# 165EVAL_REV_B.net
KiCad netlist of a schematic drawn in EAGLE
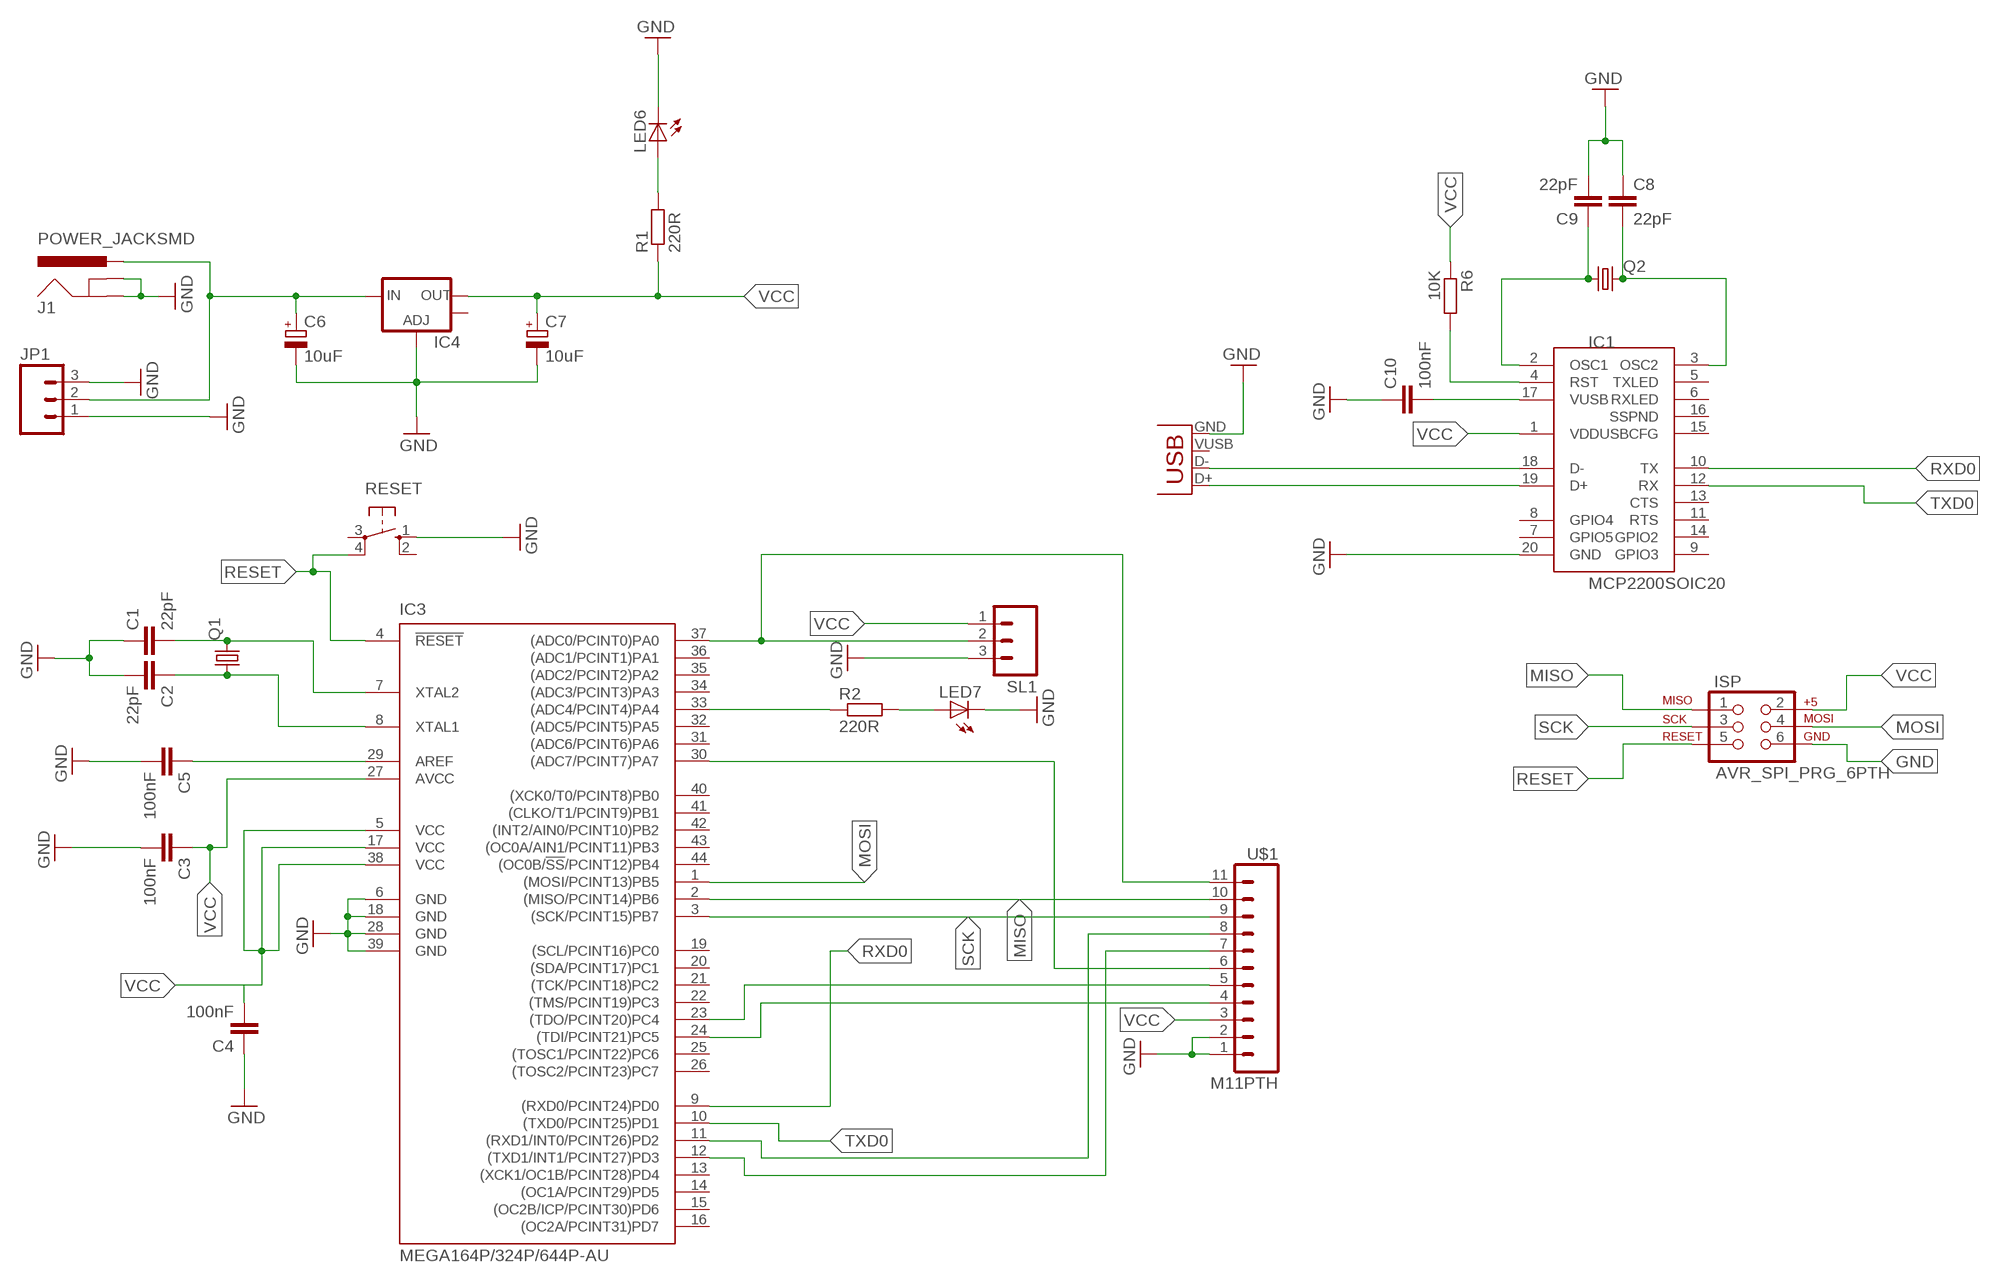
[diagram p0: schematic, sheet 1]

(export (version "E")
  (design (tool "Eeschema 10.0.6"))
  (components
    (comp (ref "C1")
      (value "22pF")
      (footprint "eagle-import:C0805K")
      (libsource (lib "eagle-import") (part "C-EUC0805K"))
    )
    (comp (ref "C2")
      (value "22pF")
      (footprint "eagle-import:C0805K")
      (libsource (lib "eagle-import") (part "C-EUC0805K"))
    )
    (comp (ref "C3")
      (value "100nF")
      (footprint "eagle-import:C0805K")
      (libsource (lib "eagle-import") (part "C-EUC0805K"))
    )
    (comp (ref "C4")
      (value "100nF")
      (footprint "eagle-import:C0805K")
      (libsource (lib "eagle-import") (part "C-EUC0805K"))
    )
    (comp (ref "C5")
      (value "100nF")
      (footprint "eagle-import:C0805K")
      (libsource (lib "eagle-import") (part "C-EUC0805K"))
    )
    (comp (ref "C6")
      (value "10uF")
      (footprint "eagle-import:CT6032")
      (libsource (lib "eagle-import") (part "CPOL-EUCT6032"))
    )
    (comp (ref "C7")
      (value "10uF")
      (footprint "eagle-import:CT6032")
      (libsource (lib "eagle-import") (part "CPOL-EUCT6032"))
    )
    (comp (ref "C8")
      (value "22pF")
      (footprint "eagle-import:C0805K")
      (libsource (lib "eagle-import") (part "C-EUC0805K"))
    )
    (comp (ref "C9")
      (value "22pF")
      (footprint "eagle-import:C0805K")
      (libsource (lib "eagle-import") (part "C-EUC0805K"))
    )
    (comp (ref "C10")
      (value "100nF")
      (footprint "eagle-import:C0805K")
      (libsource (lib "eagle-import") (part "C-EUC0805K"))
    )
    (comp (ref "IC1")
      (value "MCP2200SOIC20")
      (footprint "eagle-import:SOIC20")
      (libsource (lib "eagle-import") (part "MCP2200SOIC20"))
    )
    (comp (ref "IC3")
      (value "MEGA164P/324P/644P-AU")
      (footprint "eagle-import:TQFP44")
      (libsource (lib "eagle-import") (part "MEGA164P/324P/644P-AU"))
    )
    (comp (ref "IC4")
      (value "V_REG_LM1117SOT223")
      (footprint "eagle-import:SOT223")
      (libsource (lib "eagle-import") (part "V_REG_LM1117SOT223"))
    )
    (comp (ref "ISP")
      (value "AVR_SPI_PRG_6PTH")
      (footprint "eagle-import:2X3")
      (libsource (lib "eagle-import") (part "AVR_SPI_PRG_6PTH"))
    )
    (comp (ref "J1")
      (value "POWER_JACKSMD")
      (footprint "eagle-import:POWER_JACK_SMD")
      (libsource (lib "eagle-import") (part "POWER_JACKSMD"))
    )
    (comp (ref "JP1")
      (value "M03PTH")
      (footprint "eagle-import:1X03")
      (libsource (lib "eagle-import") (part "M03PTH"))
    )
    (comp (ref "LED6")
      (value "LEDSMT1206")
      (footprint "eagle-import:1206")
      (libsource (lib "eagle-import") (part "LEDSMT1206"))
    )
    (comp (ref "LED7")
      (value "LEDSMT1206")
      (footprint "eagle-import:1206")
      (libsource (lib "eagle-import") (part "LEDSMT1206"))
    )
    (comp (ref "Q1")
      (value "CRYSTALSM49")
      (footprint "eagle-import:SM49")
      (libsource (lib "eagle-import") (part "CRYSTALSM49"))
    )
    (comp (ref "Q2")
      (value "CRYSTALSM49")
      (footprint "eagle-import:SM49")
      (libsource (lib "eagle-import") (part "CRYSTALSM49"))
    )
    (comp (ref "R1")
      (value "220R")
      (footprint "eagle-import:R1206")
      (libsource (lib "eagle-import") (part "R-EU_R1206"))
    )
    (comp (ref "R2")
      (value "220R")
      (footprint "eagle-import:R1206")
      (libsource (lib "eagle-import") (part "R-EU_R1206"))
    )
    (comp (ref "R6")
      (value "10K")
      (footprint "eagle-import:R1206")
      (libsource (lib "eagle-import") (part "R-EU_R1206"))
    )
    (comp (ref "RESET")
      (value "10-XX")
      (footprint "eagle-import:B3F-10XX")
      (fields (field (name "MPN") "B3F-1000"))
      (libsource (lib "eagle-import") (part "10-XX"))
    )
    (comp (ref "SL1")
      (value "M03")
      (footprint "eagle-import:03P")
      (libsource (lib "eagle-import") (part "M03"))
    )
    (comp (ref "U$1")
      (value "M11PTH")
      (footprint "eagle-import:1X11")
      (libsource (lib "eagle-import") (part "M11PTH"))
    )
    (comp (ref "USB")
      (value "USB-B-S")
      (footprint "eagle-import:USB-B-SMT")
      (libsource (lib "eagle-import") (part "USB-B-S"))
    )
  )
  (nets
    (net (code "1") (name "GND") (class "Default")
      (node (ref "C1") (pin "1") (pinfunction "1_1") (pintype "passive"))
      (node (ref "C10") (pin "1") (pinfunction "1_1") (pintype "passive"))
      (node (ref "C2") (pin "2") (pinfunction "2_2") (pintype "passive"))
      (node (ref "C3") (pin "2") (pinfunction "2_2") (pintype "passive"))
      (node (ref "C4") (pin "1") (pinfunction "1_1") (pintype "passive"))
      (node (ref "C5") (pin "2") (pinfunction "2_2") (pintype "passive"))
      (node (ref "C6") (pin "-") (pinfunction "-_-") (pintype "passive"))
      (node (ref "C7") (pin "-") (pinfunction "-_-") (pintype "passive"))
      (node (ref "C8") (pin "1") (pinfunction "1_1") (pintype "passive"))
      (node (ref "C9") (pin "2") (pinfunction "2_2") (pintype "passive"))
      (node (ref "IC1") (pin "20") (pinfunction "GND_20") (pintype "bidirectional"))
      (node (ref "IC3") (pin "18") (pinfunction "GND_18") (pintype "power_in"))
      (node (ref "IC3") (pin "28") (pinfunction "GND_28") (pintype "power_in"))
      (node (ref "IC3") (pin "39") (pinfunction "GND_39") (pintype "power_in"))
      (node (ref "IC3") (pin "6") (pinfunction "GND_6") (pintype "power_in"))
      (node (ref "IC4") (pin "1") (pinfunction "ADJ_1") (pintype "input"))
      (node (ref "ISP") (pin "6") (pinfunction "6_6") (pintype "passive"))
      (node (ref "J1") (pin "GND") (pinfunction "GNDBREAK_GND") (pintype "bidirectional"))
      (node (ref "J1") (pin "P$4") (pinfunction "GND_P$4") (pintype "bidirectional"))
      (node (ref "JP1") (pin "1") (pinfunction "1_1") (pintype "passive"))
      (node (ref "JP1") (pin "3") (pinfunction "3_3") (pintype "passive"))
      (node (ref "LED6") (pin "C") (pinfunction "C_C") (pintype "passive"))
      (node (ref "LED7") (pin "C") (pinfunction "C_C") (pintype "passive"))
      (node (ref "RESET") (pin "1") (pinfunction "S_1") (pintype "passive"))
      (node (ref "SL1") (pin "3") (pinfunction "3_3") (pintype "passive"))
      (node (ref "U$1") (pin "1") (pinfunction "1_1") (pintype "passive"))
      (node (ref "U$1") (pin "2") (pinfunction "2_2") (pintype "passive"))
      (node (ref "USB") (pin "GND") (pinfunction "GND_GND") (pintype "bidirectional"))
    )
    (net (code "2") (name "MISO") (class "Default")
      (node (ref "IC3") (pin "2") (pinfunction "(MISO/PCINT14)PB6_2") (pintype "bidirectional"))
      (node (ref "ISP") (pin "1") (pinfunction "1_1") (pintype "passive"))
      (node (ref "U$1") (pin "10") (pinfunction "10_10") (pintype "passive"))
    )
    (net (code "3") (name "MOSI") (class "Default")
      (node (ref "IC3") (pin "1") (pinfunction "(MOSI/PCINT13)PB5_1") (pintype "bidirectional"))
      (node (ref "ISP") (pin "4") (pinfunction "4_4") (pintype "passive"))
    )
    (net (code "4") (name "Net-(IC1-D+)") (class "Default")
      (node (ref "IC1") (pin "19") (pinfunction "D+_19") (pintype "bidirectional"))
      (node (ref "USB") (pin "D+") (pinfunction "D+_D+") (pintype "bidirectional"))
    )
    (net (code "5") (name "Net-(IC1-D-)") (class "Default")
      (node (ref "IC1") (pin "18") (pinfunction "D-_18") (pintype "bidirectional"))
      (node (ref "USB") (pin "D-") (pinfunction "D-_D-") (pintype "bidirectional"))
    )
    (net (code "6") (name "Net-(IC1-OSC1)") (class "Default")
      (node (ref "C9") (pin "1") (pinfunction "1_1") (pintype "passive"))
      (node (ref "IC1") (pin "2") (pinfunction "OSC1_2") (pintype "bidirectional"))
      (node (ref "Q2") (pin "1") (pinfunction "1_1") (pintype "passive"))
    )
    (net (code "7") (name "Net-(IC1-OSC2)") (class "Default")
      (node (ref "C8") (pin "2") (pinfunction "2_2") (pintype "passive"))
      (node (ref "IC1") (pin "3") (pinfunction "OSC2_3") (pintype "bidirectional"))
      (node (ref "Q2") (pin "2") (pinfunction "2_2") (pintype "passive"))
    )
    (net (code "8") (name "Net-(IC1-RST)") (class "Default")
      (node (ref "IC1") (pin "4") (pinfunction "RST_4") (pintype "bidirectional"))
      (node (ref "R6") (pin "2") (pinfunction "2_2") (pintype "passive"))
    )
    (net (code "9") (name "Net-(IC1-VUSB)") (class "Default")
      (node (ref "C10") (pin "2") (pinfunction "2_2") (pintype "passive"))
      (node (ref "IC1") (pin "17") (pinfunction "VUSB_17") (pintype "bidirectional"))
    )
    (net (code "10") (name "Net-(IC3-(ADC0{slash}PCINT0)PA0)") (class "Default")
      (node (ref "IC3") (pin "37") (pinfunction "(ADC0/PCINT0)PA0_37") (pintype "bidirectional"))
      (node (ref "SL1") (pin "2") (pinfunction "2_2") (pintype "passive"))
      (node (ref "U$1") (pin "11") (pinfunction "11_11") (pintype "passive"))
    )
    (net (code "11") (name "Net-(IC3-(ADC4{slash}PCINT4)PA4)") (class "Default")
      (node (ref "IC3") (pin "33") (pinfunction "(ADC4/PCINT4)PA4_33") (pintype "bidirectional"))
      (node (ref "R2") (pin "1") (pinfunction "1_1") (pintype "passive"))
    )
    (net (code "12") (name "Net-(IC3-(ADC7{slash}PCINT7)PA7)") (class "Default")
      (node (ref "IC3") (pin "30") (pinfunction "(ADC7/PCINT7)PA7_30") (pintype "bidirectional"))
      (node (ref "U$1") (pin "6") (pinfunction "6_6") (pintype "passive"))
    )
    (net (code "13") (name "Net-(IC3-(RXD1{slash}INT0{slash}PCINT26)PD2)") (class "Default")
      (node (ref "IC3") (pin "11") (pinfunction "(RXD1/INT0/PCINT26)PD2_11") (pintype "bidirectional"))
      (node (ref "U$1") (pin "8") (pinfunction "8_8") (pintype "passive"))
    )
    (net (code "14") (name "Net-(IC3-(TDI{slash}PCINT21)PC5)") (class "Default")
      (node (ref "IC3") (pin "24") (pinfunction "(TDI/PCINT21)PC5_24") (pintype "bidirectional"))
      (node (ref "U$1") (pin "4") (pinfunction "4_4") (pintype "passive"))
    )
    (net (code "15") (name "Net-(IC3-(TDO{slash}PCINT20)PC4)") (class "Default")
      (node (ref "IC3") (pin "23") (pinfunction "(TDO/PCINT20)PC4_23") (pintype "bidirectional"))
      (node (ref "U$1") (pin "5") (pinfunction "5_5") (pintype "passive"))
    )
    (net (code "16") (name "Net-(IC3-(TXD1{slash}INT1{slash}PCINT27)PD3)") (class "Default")
      (node (ref "IC3") (pin "12") (pinfunction "(TXD1/INT1/PCINT27)PD3_12") (pintype "bidirectional"))
      (node (ref "U$1") (pin "7") (pinfunction "7_7") (pintype "passive"))
    )
    (net (code "17") (name "Net-(IC3-AREF)") (class "Default")
      (node (ref "C5") (pin "1") (pinfunction "1_1") (pintype "passive"))
      (node (ref "IC3") (pin "29") (pinfunction "AREF_29") (pintype "power_in"))
    )
    (net (code "18") (name "Net-(IC3-XTAL1)") (class "Default")
      (node (ref "C2") (pin "1") (pinfunction "1_1") (pintype "passive"))
      (node (ref "IC3") (pin "8") (pinfunction "XTAL1_8") (pintype "input"))
      (node (ref "Q1") (pin "1") (pinfunction "1_1") (pintype "passive"))
    )
    (net (code "19") (name "Net-(IC3-XTAL2)") (class "Default")
      (node (ref "C1") (pin "2") (pinfunction "2_2") (pintype "passive"))
      (node (ref "IC3") (pin "7") (pinfunction "XTAL2_7") (pintype "output"))
      (node (ref "Q1") (pin "2") (pinfunction "2_2") (pintype "passive"))
    )
    (net (code "20") (name "Net-(IC4-IN)") (class "Default")
      (node (ref "C6") (pin "+") (pinfunction "+_+") (pintype "passive"))
      (node (ref "IC4") (pin "3") (pinfunction "IN_3") (pintype "input"))
      (node (ref "J1") (pin "VIN0") (pinfunction "PWR_VIN0") (pintype "bidirectional"))
      (node (ref "JP1") (pin "2") (pinfunction "2_2") (pintype "passive"))
    )
    (net (code "21") (name "Net-(LED6-PadA)") (class "Default")
      (node (ref "LED6") (pin "A") (pinfunction "A_A") (pintype "passive"))
      (node (ref "R1") (pin "2") (pinfunction "2_2") (pintype "passive"))
    )
    (net (code "22") (name "Net-(LED7-PadA)") (class "Default")
      (node (ref "LED7") (pin "A") (pinfunction "A_A") (pintype "passive"))
      (node (ref "R2") (pin "2") (pinfunction "2_2") (pintype "passive"))
    )
    (net (code "23") (name "RESET") (class "Default")
      (node (ref "IC3") (pin "4") (pinfunction "~{RESET}_4") (pintype "input"))
      (node (ref "ISP") (pin "5") (pinfunction "5_5") (pintype "passive"))
      (node (ref "RESET") (pin "4") (pinfunction "P1_4") (pintype "passive"))
    )
    (net (code "24") (name "RXD0") (class "Default")
      (node (ref "IC1") (pin "10") (pinfunction "TX_10") (pintype "bidirectional"))
      (node (ref "IC3") (pin "9") (pinfunction "(RXD0/PCINT24)PD0_9") (pintype "bidirectional"))
    )
    (net (code "25") (name "SCK") (class "Default")
      (node (ref "IC3") (pin "3") (pinfunction "(SCK/PCINT15)PB7_3") (pintype "bidirectional"))
      (node (ref "ISP") (pin "3") (pinfunction "3_3") (pintype "passive"))
      (node (ref "U$1") (pin "9") (pinfunction "9_9") (pintype "passive"))
    )
    (net (code "26") (name "TXD0") (class "Default")
      (node (ref "IC1") (pin "12") (pinfunction "RX_12") (pintype "bidirectional"))
      (node (ref "IC3") (pin "10") (pinfunction "(TXD0/PCINT25)PD1_10") (pintype "bidirectional"))
    )
    (net (code "27") (name "VCC") (class "Default")
      (node (ref "C3") (pin "1") (pinfunction "1_1") (pintype "passive"))
      (node (ref "C4") (pin "2") (pinfunction "2_2") (pintype "passive"))
      (node (ref "C7") (pin "+") (pinfunction "+_+") (pintype "passive"))
      (node (ref "IC1") (pin "1") (pinfunction "VDD_1") (pintype "bidirectional"))
      (node (ref "IC3") (pin "17") (pinfunction "VCC_17") (pintype "power_in"))
      (node (ref "IC3") (pin "27") (pinfunction "AVCC_27") (pintype "power_in"))
      (node (ref "IC3") (pin "38") (pinfunction "VCC_38") (pintype "power_in"))
      (node (ref "IC3") (pin "5") (pinfunction "VCC_5") (pintype "power_in"))
      (node (ref "IC4") (pin "2") (pinfunction "OUT_2") (pintype "output"))
      (node (ref "ISP") (pin "2") (pinfunction "2_2") (pintype "passive"))
      (node (ref "R1") (pin "1") (pinfunction "1_1") (pintype "passive"))
      (node (ref "R6") (pin "1") (pinfunction "1_1") (pintype "passive"))
      (node (ref "SL1") (pin "1") (pinfunction "1_1") (pintype "passive"))
      (node (ref "U$1") (pin "3") (pinfunction "3_3") (pintype "passive"))
    )
    (net (code "28") (name "unconnected-(IC1-CTS-Pad13)") (class "Default")
      (node (ref "IC1") (pin "13") (pinfunction "CTS_13") (pintype "bidirectional"))
    )
    (net (code "29") (name "unconnected-(IC1-GPIO2-Pad14)") (class "Default")
      (node (ref "IC1") (pin "14") (pinfunction "GPIO2_14") (pintype "bidirectional"))
    )
    (net (code "30") (name "unconnected-(IC1-GPIO3-Pad9)") (class "Default")
      (node (ref "IC1") (pin "9") (pinfunction "GPIO3_9") (pintype "bidirectional"))
    )
    (net (code "31") (name "unconnected-(IC1-GPIO4-Pad8)") (class "Default")
      (node (ref "IC1") (pin "8") (pinfunction "GPIO4_8") (pintype "bidirectional"))
    )
    (net (code "32") (name "unconnected-(IC1-GPIO5-Pad7)") (class "Default")
      (node (ref "IC1") (pin "7") (pinfunction "GPIO5_7") (pintype "bidirectional"))
    )
    (net (code "33") (name "unconnected-(IC1-RTS-Pad11)") (class "Default")
      (node (ref "IC1") (pin "11") (pinfunction "RTS_11") (pintype "bidirectional"))
    )
    (net (code "34") (name "unconnected-(IC1-RXLED-Pad6)") (class "Default")
      (node (ref "IC1") (pin "6") (pinfunction "RXLED_6") (pintype "bidirectional"))
    )
    (net (code "35") (name "unconnected-(IC1-SSPND-Pad16)") (class "Default")
      (node (ref "IC1") (pin "16") (pinfunction "SSPND_16") (pintype "bidirectional"))
    )
    (net (code "36") (name "unconnected-(IC1-TXLED-Pad5)") (class "Default")
      (node (ref "IC1") (pin "5") (pinfunction "TXLED_5") (pintype "bidirectional"))
    )
    (net (code "37") (name "unconnected-(IC1-USBCFG-Pad15)") (class "Default")
      (node (ref "IC1") (pin "15") (pinfunction "USBCFG_15") (pintype "bidirectional"))
    )
    (net (code "38") (name "unconnected-(IC3-(ADC1{slash}PCINT1)PA1-Pad36)") (class "Default")
      (node (ref "IC3") (pin "36") (pinfunction "(ADC1/PCINT1)PA1_36") (pintype "bidirectional"))
    )
    (net (code "39") (name "unconnected-(IC3-(ADC2{slash}PCINT2)PA2-Pad35)") (class "Default")
      (node (ref "IC3") (pin "35") (pinfunction "(ADC2/PCINT2)PA2_35") (pintype "bidirectional"))
    )
    (net (code "40") (name "unconnected-(IC3-(ADC3{slash}PCINT3)PA3-Pad34)") (class "Default")
      (node (ref "IC3") (pin "34") (pinfunction "(ADC3/PCINT3)PA3_34") (pintype "bidirectional"))
    )
    (net (code "41") (name "unconnected-(IC3-(ADC5{slash}PCINT5)PA5-Pad32)") (class "Default")
      (node (ref "IC3") (pin "32") (pinfunction "(ADC5/PCINT5)PA5_32") (pintype "bidirectional"))
    )
    (net (code "42") (name "unconnected-(IC3-(ADC6{slash}PCINT6)PA6-Pad31)") (class "Default")
      (node (ref "IC3") (pin "31") (pinfunction "(ADC6/PCINT6)PA6_31") (pintype "bidirectional"))
    )
    (net (code "43") (name "unconnected-(IC3-(CLKO{slash}T1{slash}PCINT9)PB1-Pad41)") (class "Default")
      (node (ref "IC3") (pin "41") (pinfunction "(CLKO/T1/PCINT9)PB1_41") (pintype "bidirectional"))
    )
    (net (code "44") (name "unconnected-(IC3-(INT2{slash}AIN0{slash}PCINT10)PB2-Pad42)") (class "Default")
      (node (ref "IC3") (pin "42") (pinfunction "(INT2/AIN0/PCINT10)PB2_42") (pintype "bidirectional"))
    )
    (net (code "45") (name "unconnected-(IC3-(OC0A{slash}AIN1{slash}PCINT11)PB3-Pad43)") (class "Default")
      (node (ref "IC3") (pin "43") (pinfunction "(OC0A/AIN1/PCINT11)PB3_43") (pintype "bidirectional"))
    )
    (net (code "46") (name "unconnected-(IC3-(OC0B{slash}~{SS}{slash}PCINT12)PB4-Pad44)") (class "Default")
      (node (ref "IC3") (pin "44") (pinfunction "(OC0B/~{SS}/PCINT12)PB4_44") (pintype "bidirectional"))
    )
    (net (code "47") (name "unconnected-(IC3-(OC1A{slash}PCINT29)PD5-Pad14)") (class "Default")
      (node (ref "IC3") (pin "14") (pinfunction "(OC1A/PCINT29)PD5_14") (pintype "bidirectional"))
    )
    (net (code "48") (name "unconnected-(IC3-(OC2A{slash}PCINT31)PD7-Pad16)") (class "Default")
      (node (ref "IC3") (pin "16") (pinfunction "(OC2A/PCINT31)PD7_16") (pintype "bidirectional"))
    )
    (net (code "49") (name "unconnected-(IC3-(OC2B{slash}ICP{slash}PCINT30)PD6-Pad15)") (class "Default")
      (node (ref "IC3") (pin "15") (pinfunction "(OC2B/ICP/PCINT30)PD6_15") (pintype "bidirectional"))
    )
    (net (code "50") (name "unconnected-(IC3-(SCL{slash}PCINT16)PC0-Pad19)") (class "Default")
      (node (ref "IC3") (pin "19") (pinfunction "(SCL/PCINT16)PC0_19") (pintype "bidirectional"))
    )
    (net (code "51") (name "unconnected-(IC3-(SDA{slash}PCINT17)PC1-Pad20)") (class "Default")
      (node (ref "IC3") (pin "20") (pinfunction "(SDA/PCINT17)PC1_20") (pintype "bidirectional"))
    )
    (net (code "52") (name "unconnected-(IC3-(TCK{slash}PCINT18)PC2-Pad21)") (class "Default")
      (node (ref "IC3") (pin "21") (pinfunction "(TCK/PCINT18)PC2_21") (pintype "bidirectional"))
    )
    (net (code "53") (name "unconnected-(IC3-(TMS{slash}PCINT19)PC3-Pad22)") (class "Default")
      (node (ref "IC3") (pin "22") (pinfunction "(TMS/PCINT19)PC3_22") (pintype "bidirectional"))
    )
    (net (code "54") (name "unconnected-(IC3-(TOSC1{slash}PCINT22)PC6-Pad25)") (class "Default")
      (node (ref "IC3") (pin "25") (pinfunction "(TOSC1/PCINT22)PC6_25") (pintype "bidirectional"))
    )
    (net (code "55") (name "unconnected-(IC3-(TOSC2{slash}PCINT23)PC7-Pad26)") (class "Default")
      (node (ref "IC3") (pin "26") (pinfunction "(TOSC2/PCINT23)PC7_26") (pintype "bidirectional"))
    )
    (net (code "56") (name "unconnected-(IC3-(XCK0{slash}T0{slash}PCINT8)PB0-Pad40)") (class "Default")
      (node (ref "IC3") (pin "40") (pinfunction "(XCK0/T0/PCINT8)PB0_40") (pintype "bidirectional"))
    )
    (net (code "57") (name "unconnected-(IC3-(XCK1{slash}OC1B{slash}PCINT28)PD4-Pad13)") (class "Default")
      (node (ref "IC3") (pin "13") (pinfunction "(XCK1/OC1B/PCINT28)PD4_13") (pintype "bidirectional"))
    )
    (net (code "58") (name "unconnected-(IC4-OUT-Pad4)") (class "Default")
      (node (ref "IC4") (pin "4") (pinfunction "OUT_4") (pintype "output"))
    )
    (net (code "59") (name "unconnected-(RESET-P-Pad3)") (class "Default")
      (node (ref "RESET") (pin "3") (pinfunction "P_3") (pintype "passive"))
    )
    (net (code "60") (name "unconnected-(RESET-S1-Pad2)") (class "Default")
      (node (ref "RESET") (pin "2") (pinfunction "S1_2") (pintype "passive"))
    )
    (net (code "61") (name "unconnected-(USB-VBUS-PadVUSB)") (class "Default")
      (node (ref "USB") (pin "VUSB") (pinfunction "VBUS_VUSB") (pintype "bidirectional"))
    )
  )
)
